# SUSTAINA-Power-Supply-Switching-Board.net
KiCad netlist of a schematic drawn in EAGLE
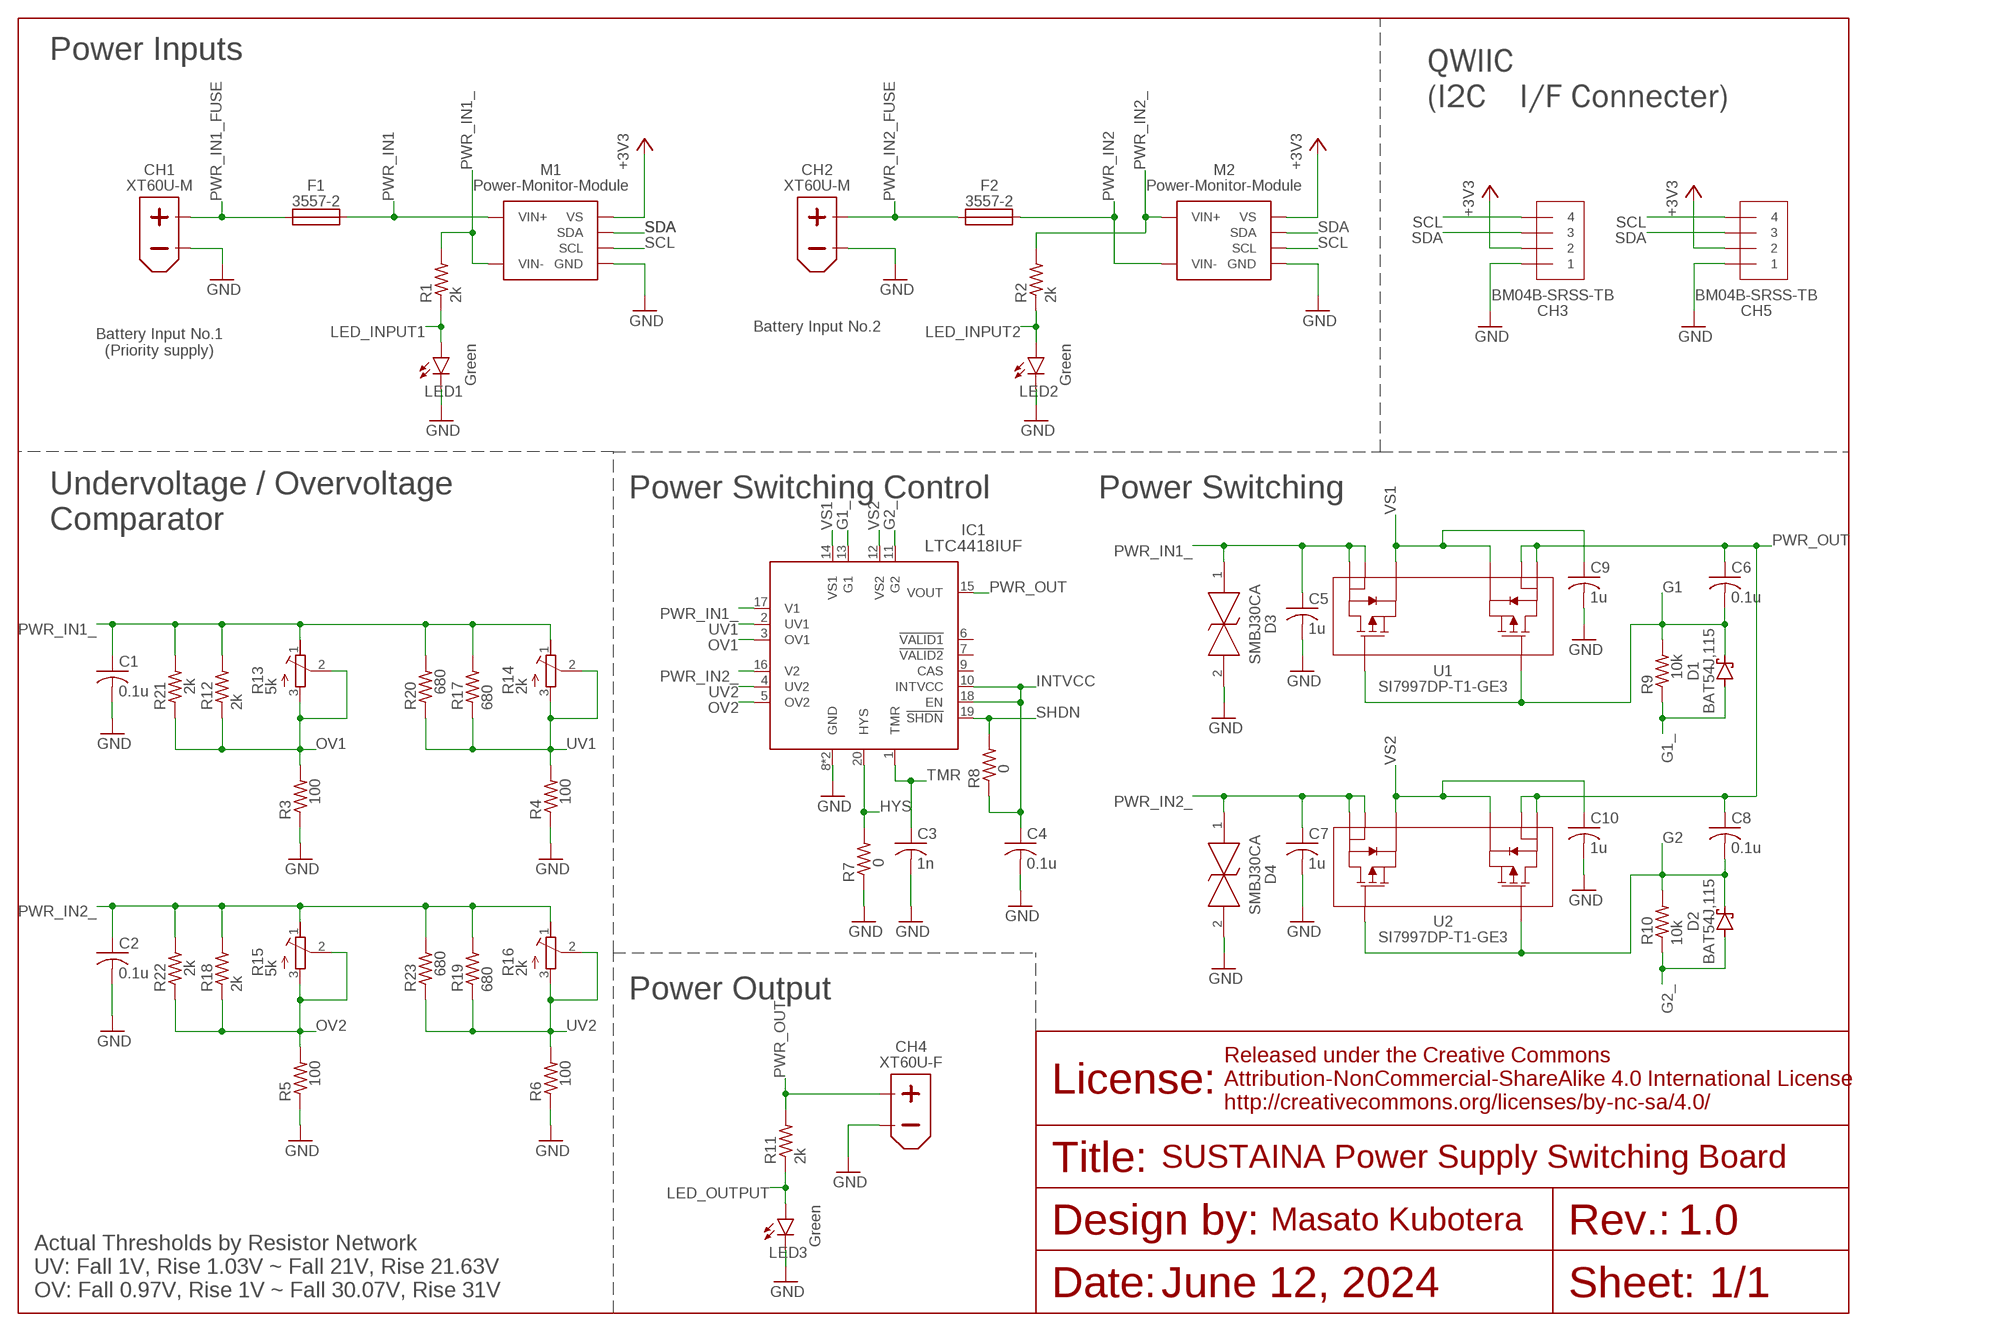
[diagram p0: schematic, sheet 1]

(export (version "E")
  (design (tool "Eeschema 10.0.6"))
  (components
    (comp (ref "C1")
      (value "0.1u")
      (footprint "eagle-import:C0603")
      (libsource (lib "eagle-import") (part "C-USC0603"))
    )
    (comp (ref "C2")
      (value "0.1u")
      (footprint "eagle-import:C0603")
      (libsource (lib "eagle-import") (part "C-USC0603"))
    )
    (comp (ref "C3")
      (value "1n")
      (footprint "eagle-import:C0603")
      (libsource (lib "eagle-import") (part "C-USC0603"))
    )
    (comp (ref "C4")
      (value "0.1u")
      (footprint "eagle-import:C0603")
      (libsource (lib "eagle-import") (part "C-USC0603"))
    )
    (comp (ref "C5")
      (value "1u")
      (footprint "eagle-import:C0603")
      (libsource (lib "eagle-import") (part "C-USC0603"))
    )
    (comp (ref "C6")
      (value "0.1u")
      (footprint "eagle-import:C0603")
      (libsource (lib "eagle-import") (part "C-USC0603"))
    )
    (comp (ref "C7")
      (value "1u")
      (footprint "eagle-import:C0603")
      (libsource (lib "eagle-import") (part "C-USC0603"))
    )
    (comp (ref "C8")
      (value "0.1u")
      (footprint "eagle-import:C0603")
      (libsource (lib "eagle-import") (part "C-USC0603"))
    )
    (comp (ref "C9")
      (value "1u")
      (footprint "eagle-import:C0603")
      (libsource (lib "eagle-import") (part "C-USC0603"))
    )
    (comp (ref "C10")
      (value "1u")
      (footprint "eagle-import:C0603")
      (libsource (lib "eagle-import") (part "C-USC0603"))
    )
    (comp (ref "CH1")
      (value "XT60U-M")
      (footprint "eagle-import:XT60U-M")
      (libsource (lib "eagle-import") (part "XT60U-M"))
    )
    (comp (ref "CH2")
      (value "XT60U-M")
      (footprint "eagle-import:XT60U-M")
      (libsource (lib "eagle-import") (part "XT60U-M"))
    )
    (comp (ref "CH3")
      (value "BM04B-SRSS-TB")
      (footprint "eagle-import:BM04B-SRSS-TB")
      (libsource (lib "eagle-import") (part "BM04B-SRSS-TB"))
    )
    (comp (ref "CH4")
      (value "XT60U-F")
      (footprint "eagle-import:XT60U-F")
      (libsource (lib "eagle-import") (part "XT60U-F"))
    )
    (comp (ref "CH5")
      (value "BM04B-SRSS-TB")
      (footprint "eagle-import:BM04B-SRSS-TB")
      (libsource (lib "eagle-import") (part "BM04B-SRSS-TB"))
    )
    (comp (ref "D1")
      (value "BAT54J,115")
      (footprint "eagle-import:SOD-323-2")
      (libsource (lib "eagle-import") (part "BAT54J,115"))
    )
    (comp (ref "D2")
      (value "BAT54J,115")
      (footprint "eagle-import:SOD-323-2")
      (libsource (lib "eagle-import") (part "BAT54J,115"))
    )
    (comp (ref "D3")
      (value "SMBJ30CA")
      (footprint "eagle-import:SMBJ30CA")
      (libsource (lib "eagle-import") (part "SMBJ30CA"))
    )
    (comp (ref "D4")
      (value "SMBJ30CA")
      (footprint "eagle-import:SMBJ30CA")
      (libsource (lib "eagle-import") (part "SMBJ30CA"))
    )
    (comp (ref "F1")
      (value "3557-2")
      (footprint "eagle-import:3557-2")
      (libsource (lib "eagle-import") (part "3557-2"))
    )
    (comp (ref "F2")
      (value "3557-2")
      (footprint "eagle-import:3557-2")
      (libsource (lib "eagle-import") (part "3557-2"))
    )
    (comp (ref "IC1")
      (value "LTC4418IUF")
      (footprint "eagle-import:LTC4418IUF")
      (libsource (lib "eagle-import") (part "LTC4418IUF"))
    )
    (comp (ref "LED1")
      (value "Green")
      (footprint "eagle-import:SML0603")
      (libsource (lib "eagle-import") (part "LEDSML0603"))
    )
    (comp (ref "LED2")
      (value "Green")
      (footprint "eagle-import:SML0603")
      (libsource (lib "eagle-import") (part "LEDSML0603"))
    )
    (comp (ref "LED3")
      (value "Green")
      (footprint "eagle-import:SML0603")
      (libsource (lib "eagle-import") (part "LEDSML0603"))
    )
    (comp (ref "M1")
      (value "POWER-MONITOR-MODULE")
      (footprint "eagle-import:POWER-MONITOR-MODULE")
      (libsource (lib "eagle-import") (part "POWER-MONITOR-MODULE"))
    )
    (comp (ref "M2")
      (value "POWER-MONITOR-MODULE")
      (footprint "eagle-import:POWER-MONITOR-MODULE")
      (libsource (lib "eagle-import") (part "POWER-MONITOR-MODULE"))
    )
    (comp (ref "R1")
      (value "2k")
      (footprint "eagle-import:R0603")
      (libsource (lib "eagle-import") (part "R-US_R0603"))
    )
    (comp (ref "R2")
      (value "2k")
      (footprint "eagle-import:R0603")
      (libsource (lib "eagle-import") (part "R-US_R0603"))
    )
    (comp (ref "R3")
      (value "100")
      (footprint "eagle-import:R0603")
      (libsource (lib "eagle-import") (part "R-US_R0603"))
    )
    (comp (ref "R4")
      (value "100")
      (footprint "eagle-import:R0603")
      (libsource (lib "eagle-import") (part "R-US_R0603"))
    )
    (comp (ref "R5")
      (value "100")
      (footprint "eagle-import:R0603")
      (libsource (lib "eagle-import") (part "R-US_R0603"))
    )
    (comp (ref "R6")
      (value "100")
      (footprint "eagle-import:R0603")
      (libsource (lib "eagle-import") (part "R-US_R0603"))
    )
    (comp (ref "R7")
      (value "0")
      (footprint "eagle-import:R0603")
      (libsource (lib "eagle-import") (part "R-US_R0603"))
    )
    (comp (ref "R8")
      (value "0")
      (footprint "eagle-import:R0603")
      (libsource (lib "eagle-import") (part "R-US_R0603"))
    )
    (comp (ref "R9")
      (value "10k")
      (footprint "eagle-import:R0603")
      (libsource (lib "eagle-import") (part "R-US_R0603"))
    )
    (comp (ref "R10")
      (value "10k")
      (footprint "eagle-import:R0603")
      (libsource (lib "eagle-import") (part "R-US_R0603"))
    )
    (comp (ref "R11")
      (value "2k")
      (footprint "eagle-import:R0603")
      (libsource (lib "eagle-import") (part "R-US_R0603"))
    )
    (comp (ref "R12")
      (value "2k")
      (footprint "eagle-import:0204_5")
      (libsource (lib "eagle-import") (part "R-US_0204/5"))
    )
    (comp (ref "R13")
      (value "5k")
      (footprint "eagle-import:RTRIM3006P")
      (libsource (lib "eagle-import") (part "R-TRIMM3006P"))
    )
    (comp (ref "R14")
      (value "2k")
      (footprint "eagle-import:RTRIM3006P")
      (libsource (lib "eagle-import") (part "R-TRIMM3006P"))
    )
    (comp (ref "R15")
      (value "5k")
      (footprint "eagle-import:RTRIM3006P")
      (libsource (lib "eagle-import") (part "R-TRIMM3006P"))
    )
    (comp (ref "R16")
      (value "2k")
      (footprint "eagle-import:RTRIM3006P")
      (libsource (lib "eagle-import") (part "R-TRIMM3006P"))
    )
    (comp (ref "R17")
      (value "680")
      (footprint "eagle-import:0204_5")
      (libsource (lib "eagle-import") (part "R-US_0204/5"))
    )
    (comp (ref "R18")
      (value "2k")
      (footprint "eagle-import:0204_5")
      (libsource (lib "eagle-import") (part "R-US_0204/5"))
    )
    (comp (ref "R19")
      (value "680")
      (footprint "eagle-import:0204_5")
      (libsource (lib "eagle-import") (part "R-US_0204/5"))
    )
    (comp (ref "R20")
      (value "680")
      (footprint "eagle-import:R0603")
      (libsource (lib "eagle-import") (part "R-US_R0603"))
    )
    (comp (ref "R21")
      (value "2k")
      (footprint "eagle-import:R0603")
      (libsource (lib "eagle-import") (part "R-US_R0603"))
    )
    (comp (ref "R22")
      (value "2k")
      (footprint "eagle-import:R0603")
      (libsource (lib "eagle-import") (part "R-US_R0603"))
    )
    (comp (ref "R23")
      (value "680")
      (footprint "eagle-import:R0603")
      (libsource (lib "eagle-import") (part "R-US_R0603"))
    )
    (comp (ref "U1")
      (value "SI7997DP-T1-GE3")
      (footprint "eagle-import:POWERPAK_SO-8_VIS")
      (fields (field (name "COPYRIGHT") "Copyright (C) 2024 Ultra Librarian. All rights reserved."))
      (libsource (lib "eagle-import") (part "SI7997DP-T1-GE3"))
    )
    (comp (ref "U2")
      (value "SI7997DP-T1-GE3")
      (footprint "eagle-import:POWERPAK_SO-8_VIS")
      (fields (field (name "COPYRIGHT") "Copyright (C) 2024 Ultra Librarian. All rights reserved."))
      (libsource (lib "eagle-import") (part "SI7997DP-T1-GE3"))
    )
  )
  (nets
    (net (code "1") (name "+3V3") (class "Default")
      (node (ref "CH3") (pin "2") (pinfunction "2_2") (pintype "bidirectional"))
      (node (ref "CH5") (pin "2") (pinfunction "2_2") (pintype "bidirectional"))
      (node (ref "M1") (pin "VS") (pinfunction "VS_VS") (pintype "power_in"))
      (node (ref "M2") (pin "VS") (pinfunction "VS_VS") (pintype "power_in"))
    )
    (net (code "2") (name "/G1") (class "Default")
      (node (ref "C6") (pin "2") (pinfunction "2_2") (pintype "passive"))
      (node (ref "D1") (pin "1") (pinfunction "C_1") (pintype "passive"))
      (node (ref "R9") (pin "2") (pinfunction "2_2") (pintype "passive"))
      (node (ref "U1") (pin "2") (pinfunction "G1_2") (pintype "passive"))
      (node (ref "U1") (pin "4") (pinfunction "G2_4") (pintype "passive"))
    )
    (net (code "3") (name "/G1_") (class "Default")
      (node (ref "D1") (pin "2") (pinfunction "A_2") (pintype "passive"))
      (node (ref "IC1") (pin "13") (pinfunction "G1_13") (pintype "bidirectional"))
      (node (ref "R9") (pin "1") (pinfunction "1_1") (pintype "passive"))
    )
    (net (code "4") (name "/G2") (class "Default")
      (node (ref "C8") (pin "2") (pinfunction "2_2") (pintype "passive"))
      (node (ref "D2") (pin "1") (pinfunction "C_1") (pintype "passive"))
      (node (ref "R10") (pin "2") (pinfunction "2_2") (pintype "passive"))
      (node (ref "U2") (pin "2") (pinfunction "G1_2") (pintype "passive"))
      (node (ref "U2") (pin "4") (pinfunction "G2_4") (pintype "passive"))
    )
    (net (code "5") (name "/G2_") (class "Default")
      (node (ref "D2") (pin "2") (pinfunction "A_2") (pintype "passive"))
      (node (ref "IC1") (pin "11") (pinfunction "G2_11") (pintype "bidirectional"))
      (node (ref "R10") (pin "1") (pinfunction "1_1") (pintype "passive"))
    )
    (net (code "6") (name "/HYS") (class "Default")
      (node (ref "IC1") (pin "20") (pinfunction "HYS_20") (pintype "bidirectional"))
      (node (ref "R7") (pin "2") (pinfunction "2_2") (pintype "passive"))
    )
    (net (code "7") (name "/INTVCC") (class "Default")
      (node (ref "C4") (pin "1") (pinfunction "1_1") (pintype "passive"))
      (node (ref "IC1") (pin "10") (pinfunction "INTVCC_10") (pintype "bidirectional"))
      (node (ref "IC1") (pin "18") (pinfunction "EN_18") (pintype "bidirectional"))
      (node (ref "R8") (pin "1") (pinfunction "1_1") (pintype "passive"))
    )
    (net (code "8") (name "/LED_INPUT1") (class "Default")
      (node (ref "LED1") (pin "A") (pinfunction "A_A") (pintype "passive"))
      (node (ref "R1") (pin "1") (pinfunction "1_1") (pintype "passive"))
    )
    (net (code "9") (name "/LED_INPUT2") (class "Default")
      (node (ref "LED2") (pin "A") (pinfunction "A_A") (pintype "passive"))
      (node (ref "R2") (pin "1") (pinfunction "1_1") (pintype "passive"))
    )
    (net (code "10") (name "/LED_OUTPUT") (class "Default")
      (node (ref "LED3") (pin "A") (pinfunction "A_A") (pintype "passive"))
      (node (ref "R11") (pin "1") (pinfunction "1_1") (pintype "passive"))
    )
    (net (code "11") (name "/OV1") (class "Default")
      (node (ref "IC1") (pin "3") (pinfunction "OV1_3") (pintype "bidirectional"))
      (node (ref "R12") (pin "1") (pinfunction "1_1") (pintype "passive"))
      (node (ref "R13") (pin "2") (pinfunction "S_2") (pintype "passive"))
      (node (ref "R13") (pin "3") (pinfunction "A_3") (pintype "passive"))
      (node (ref "R21") (pin "1") (pinfunction "1_1") (pintype "passive"))
      (node (ref "R3") (pin "2") (pinfunction "2_2") (pintype "passive"))
    )
    (net (code "12") (name "/OV2") (class "Default")
      (node (ref "IC1") (pin "5") (pinfunction "OV2_5") (pintype "bidirectional"))
      (node (ref "R15") (pin "2") (pinfunction "S_2") (pintype "passive"))
      (node (ref "R15") (pin "3") (pinfunction "A_3") (pintype "passive"))
      (node (ref "R18") (pin "1") (pinfunction "1_1") (pintype "passive"))
      (node (ref "R22") (pin "1") (pinfunction "1_1") (pintype "passive"))
      (node (ref "R5") (pin "2") (pinfunction "2_2") (pintype "passive"))
    )
    (net (code "13") (name "/PWR_IN1") (class "Default")
      (node (ref "F1") (pin "3") (pinfunction "2_3") (pintype "bidirectional"))
      (node (ref "F1") (pin "4") (pinfunction "2_4") (pintype "bidirectional"))
      (node (ref "M1") (pin "VIN+1") (pinfunction "VIN+_VIN+1") (pintype "power_in"))
      (node (ref "M1") (pin "VIN+10") (pinfunction "VIN+_VIN+10") (pintype "power_in"))
      (node (ref "M1") (pin "VIN+2") (pinfunction "VIN+_VIN+2") (pintype "power_in"))
      (node (ref "M1") (pin "VIN+3") (pinfunction "VIN+_VIN+3") (pintype "power_in"))
      (node (ref "M1") (pin "VIN+4") (pinfunction "VIN+_VIN+4") (pintype "power_in"))
      (node (ref "M1") (pin "VIN+5") (pinfunction "VIN+_VIN+5") (pintype "power_in"))
      (node (ref "M1") (pin "VIN+6") (pinfunction "VIN+_VIN+6") (pintype "power_in"))
      (node (ref "M1") (pin "VIN+7") (pinfunction "VIN+_VIN+7") (pintype "power_in"))
      (node (ref "M1") (pin "VIN+8") (pinfunction "VIN+_VIN+8") (pintype "power_in"))
      (node (ref "M1") (pin "VIN+9") (pinfunction "VIN+_VIN+9") (pintype "power_in"))
    )
    (net (code "14") (name "/PWR_IN1_") (class "Default")
      (node (ref "C1") (pin "1") (pinfunction "1_1") (pintype "passive"))
      (node (ref "C5") (pin "1") (pinfunction "1_1") (pintype "passive"))
      (node (ref "D3") (pin "1") (pinfunction "1_1") (pintype "bidirectional"))
      (node (ref "IC1") (pin "17") (pinfunction "V1_17") (pintype "bidirectional"))
      (node (ref "M1") (pin "VIN-1") (pinfunction "VIN-_VIN-1") (pintype "power_in"))
      (node (ref "M1") (pin "VIN-10") (pinfunction "VIN-_VIN-10") (pintype "power_in"))
      (node (ref "M1") (pin "VIN-2") (pinfunction "VIN-_VIN-2") (pintype "power_in"))
      (node (ref "M1") (pin "VIN-3") (pinfunction "VIN-_VIN-3") (pintype "power_in"))
      (node (ref "M1") (pin "VIN-4") (pinfunction "VIN-_VIN-4") (pintype "power_in"))
      (node (ref "M1") (pin "VIN-5") (pinfunction "VIN-_VIN-5") (pintype "power_in"))
      (node (ref "M1") (pin "VIN-6") (pinfunction "VIN-_VIN-6") (pintype "power_in"))
      (node (ref "M1") (pin "VIN-7") (pinfunction "VIN-_VIN-7") (pintype "power_in"))
      (node (ref "M1") (pin "VIN-8") (pinfunction "VIN-_VIN-8") (pintype "power_in"))
      (node (ref "M1") (pin "VIN-9") (pinfunction "VIN-_VIN-9") (pintype "power_in"))
      (node (ref "R1") (pin "2") (pinfunction "2_2") (pintype "passive"))
      (node (ref "R12") (pin "2") (pinfunction "2_2") (pintype "passive"))
      (node (ref "R13") (pin "1") (pinfunction "E_1") (pintype "passive"))
      (node (ref "R14") (pin "1") (pinfunction "E_1") (pintype "passive"))
      (node (ref "R17") (pin "2") (pinfunction "2_2") (pintype "passive"))
      (node (ref "R20") (pin "2") (pinfunction "2_2") (pintype "passive"))
      (node (ref "R21") (pin "2") (pinfunction "2_2") (pintype "passive"))
      (node (ref "U1") (pin "5") (pinfunction "D2_5") (pintype "passive"))
      (node (ref "U1") (pin "6") (pinfunction "D2_2_6") (pintype "passive"))
    )
    (net (code "15") (name "/PWR_IN1_FUSE") (class "Default")
      (node (ref "CH1") (pin "+") (pinfunction "+_+") (pintype "power_in"))
      (node (ref "F1") (pin "1") (pinfunction "1_1") (pintype "bidirectional"))
      (node (ref "F1") (pin "2") (pinfunction "1_2") (pintype "bidirectional"))
    )
    (net (code "16") (name "/PWR_IN2") (class "Default")
      (node (ref "F2") (pin "3") (pinfunction "2_3") (pintype "bidirectional"))
      (node (ref "F2") (pin "4") (pinfunction "2_4") (pintype "bidirectional"))
      (node (ref "M2") (pin "VIN-1") (pinfunction "VIN-_VIN-1") (pintype "power_in"))
      (node (ref "M2") (pin "VIN-10") (pinfunction "VIN-_VIN-10") (pintype "power_in"))
      (node (ref "M2") (pin "VIN-2") (pinfunction "VIN-_VIN-2") (pintype "power_in"))
      (node (ref "M2") (pin "VIN-3") (pinfunction "VIN-_VIN-3") (pintype "power_in"))
      (node (ref "M2") (pin "VIN-4") (pinfunction "VIN-_VIN-4") (pintype "power_in"))
      (node (ref "M2") (pin "VIN-5") (pinfunction "VIN-_VIN-5") (pintype "power_in"))
      (node (ref "M2") (pin "VIN-6") (pinfunction "VIN-_VIN-6") (pintype "power_in"))
      (node (ref "M2") (pin "VIN-7") (pinfunction "VIN-_VIN-7") (pintype "power_in"))
      (node (ref "M2") (pin "VIN-8") (pinfunction "VIN-_VIN-8") (pintype "power_in"))
      (node (ref "M2") (pin "VIN-9") (pinfunction "VIN-_VIN-9") (pintype "power_in"))
    )
    (net (code "17") (name "/PWR_IN2_") (class "Default")
      (node (ref "C2") (pin "1") (pinfunction "1_1") (pintype "passive"))
      (node (ref "C7") (pin "1") (pinfunction "1_1") (pintype "passive"))
      (node (ref "D4") (pin "1") (pinfunction "1_1") (pintype "bidirectional"))
      (node (ref "IC1") (pin "16") (pinfunction "V2_16") (pintype "bidirectional"))
      (node (ref "M2") (pin "VIN+1") (pinfunction "VIN+_VIN+1") (pintype "power_in"))
      (node (ref "M2") (pin "VIN+10") (pinfunction "VIN+_VIN+10") (pintype "power_in"))
      (node (ref "M2") (pin "VIN+2") (pinfunction "VIN+_VIN+2") (pintype "power_in"))
      (node (ref "M2") (pin "VIN+3") (pinfunction "VIN+_VIN+3") (pintype "power_in"))
      (node (ref "M2") (pin "VIN+4") (pinfunction "VIN+_VIN+4") (pintype "power_in"))
      (node (ref "M2") (pin "VIN+5") (pinfunction "VIN+_VIN+5") (pintype "power_in"))
      (node (ref "M2") (pin "VIN+6") (pinfunction "VIN+_VIN+6") (pintype "power_in"))
      (node (ref "M2") (pin "VIN+7") (pinfunction "VIN+_VIN+7") (pintype "power_in"))
      (node (ref "M2") (pin "VIN+8") (pinfunction "VIN+_VIN+8") (pintype "power_in"))
      (node (ref "M2") (pin "VIN+9") (pinfunction "VIN+_VIN+9") (pintype "power_in"))
      (node (ref "R15") (pin "1") (pinfunction "E_1") (pintype "passive"))
      (node (ref "R16") (pin "1") (pinfunction "E_1") (pintype "passive"))
      (node (ref "R18") (pin "2") (pinfunction "2_2") (pintype "passive"))
      (node (ref "R19") (pin "2") (pinfunction "2_2") (pintype "passive"))
      (node (ref "R2") (pin "2") (pinfunction "2_2") (pintype "passive"))
      (node (ref "R22") (pin "2") (pinfunction "2_2") (pintype "passive"))
      (node (ref "R23") (pin "2") (pinfunction "2_2") (pintype "passive"))
      (node (ref "U2") (pin "7") (pinfunction "D1_7") (pintype "passive"))
      (node (ref "U2") (pin "8") (pinfunction "D1_2_8") (pintype "passive"))
    )
    (net (code "18") (name "/PWR_IN2_FUSE") (class "Default")
      (node (ref "CH2") (pin "+") (pinfunction "+_+") (pintype "power_in"))
      (node (ref "F2") (pin "1") (pinfunction "1_1") (pintype "bidirectional"))
      (node (ref "F2") (pin "2") (pinfunction "1_2") (pintype "bidirectional"))
    )
    (net (code "19") (name "/PWR_OUT") (class "Default")
      (node (ref "C6") (pin "1") (pinfunction "1_1") (pintype "passive"))
      (node (ref "C8") (pin "1") (pinfunction "1_1") (pintype "passive"))
      (node (ref "CH4") (pin "+") (pinfunction "+_+") (pintype "power_in"))
      (node (ref "IC1") (pin "15") (pinfunction "VOUT_15") (pintype "bidirectional"))
      (node (ref "R11") (pin "2") (pinfunction "2_2") (pintype "passive"))
      (node (ref "U1") (pin "7") (pinfunction "D1_7") (pintype "passive"))
      (node (ref "U1") (pin "8") (pinfunction "D1_2_8") (pintype "passive"))
      (node (ref "U2") (pin "5") (pinfunction "D2_5") (pintype "passive"))
      (node (ref "U2") (pin "6") (pinfunction "D2_2_6") (pintype "passive"))
    )
    (net (code "20") (name "/SCL") (class "Default")
      (node (ref "CH3") (pin "4") (pinfunction "4_4") (pintype "bidirectional"))
      (node (ref "CH5") (pin "4") (pinfunction "4_4") (pintype "bidirectional"))
      (node (ref "M1") (pin "SCL") (pinfunction "SCL_SCL") (pintype "bidirectional"))
      (node (ref "M2") (pin "SCL") (pinfunction "SCL_SCL") (pintype "bidirectional"))
    )
    (net (code "21") (name "/SDA") (class "Default")
      (node (ref "CH3") (pin "3") (pinfunction "3_3") (pintype "bidirectional"))
      (node (ref "CH5") (pin "3") (pinfunction "3_3") (pintype "bidirectional"))
      (node (ref "M1") (pin "SDA") (pinfunction "SDA_SDA") (pintype "bidirectional"))
      (node (ref "M2") (pin "SDA") (pinfunction "SDA_SDA") (pintype "bidirectional"))
    )
    (net (code "22") (name "/SHDN") (class "Default")
      (node (ref "IC1") (pin "19") (pinfunction "~{SHDN}_19") (pintype "bidirectional"))
      (node (ref "R8") (pin "2") (pinfunction "2_2") (pintype "passive"))
    )
    (net (code "23") (name "/TMR") (class "Default")
      (node (ref "C3") (pin "1") (pinfunction "1_1") (pintype "passive"))
      (node (ref "IC1") (pin "1") (pinfunction "TMR_1") (pintype "bidirectional"))
    )
    (net (code "24") (name "/UV1") (class "Default")
      (node (ref "IC1") (pin "2") (pinfunction "UV1_2") (pintype "bidirectional"))
      (node (ref "R14") (pin "2") (pinfunction "S_2") (pintype "passive"))
      (node (ref "R14") (pin "3") (pinfunction "A_3") (pintype "passive"))
      (node (ref "R17") (pin "1") (pinfunction "1_1") (pintype "passive"))
      (node (ref "R20") (pin "1") (pinfunction "1_1") (pintype "passive"))
      (node (ref "R4") (pin "2") (pinfunction "2_2") (pintype "passive"))
    )
    (net (code "25") (name "/UV2") (class "Default")
      (node (ref "IC1") (pin "4") (pinfunction "UV2_4") (pintype "bidirectional"))
      (node (ref "R16") (pin "2") (pinfunction "S_2") (pintype "passive"))
      (node (ref "R16") (pin "3") (pinfunction "A_3") (pintype "passive"))
      (node (ref "R19") (pin "1") (pinfunction "1_1") (pintype "passive"))
      (node (ref "R23") (pin "1") (pinfunction "1_1") (pintype "passive"))
      (node (ref "R6") (pin "2") (pinfunction "2_2") (pintype "passive"))
    )
    (net (code "26") (name "/VS1") (class "Default")
      (node (ref "C9") (pin "1") (pinfunction "1_1") (pintype "passive"))
      (node (ref "IC1") (pin "14") (pinfunction "VS1_14") (pintype "bidirectional"))
      (node (ref "U1") (pin "1") (pinfunction "S1_1") (pintype "passive"))
      (node (ref "U1") (pin "3") (pinfunction "S2_3") (pintype "passive"))
    )
    (net (code "27") (name "/VS2") (class "Default")
      (node (ref "C10") (pin "1") (pinfunction "1_1") (pintype "passive"))
      (node (ref "IC1") (pin "12") (pinfunction "VS2_12") (pintype "bidirectional"))
      (node (ref "U2") (pin "1") (pinfunction "S1_1") (pintype "passive"))
      (node (ref "U2") (pin "3") (pinfunction "S2_3") (pintype "passive"))
    )
    (net (code "28") (name "GND") (class "Default")
      (node (ref "C1") (pin "2") (pinfunction "2_2") (pintype "passive"))
      (node (ref "C10") (pin "2") (pinfunction "2_2") (pintype "passive"))
      (node (ref "C2") (pin "2") (pinfunction "2_2") (pintype "passive"))
      (node (ref "C3") (pin "2") (pinfunction "2_2") (pintype "passive"))
      (node (ref "C4") (pin "2") (pinfunction "2_2") (pintype "passive"))
      (node (ref "C5") (pin "2") (pinfunction "2_2") (pintype "passive"))
      (node (ref "C7") (pin "2") (pinfunction "2_2") (pintype "passive"))
      (node (ref "C9") (pin "2") (pinfunction "2_2") (pintype "passive"))
      (node (ref "CH1") (pin "-") (pinfunction "-_-") (pintype "power_in"))
      (node (ref "CH2") (pin "-") (pinfunction "-_-") (pintype "power_in"))
      (node (ref "CH3") (pin "1") (pinfunction "1_1") (pintype "bidirectional"))
      (node (ref "CH4") (pin "-") (pinfunction "-_-") (pintype "power_in"))
      (node (ref "CH5") (pin "1") (pinfunction "1_1") (pintype "bidirectional"))
      (node (ref "D3") (pin "2") (pinfunction "2_2") (pintype "bidirectional"))
      (node (ref "D4") (pin "2") (pinfunction "2_2") (pintype "bidirectional"))
      (node (ref "IC1") (pin "21") (pinfunction "GND_21") (pintype "bidirectional"))
      (node (ref "IC1") (pin "8") (pinfunction "GND_8") (pintype "bidirectional"))
      (node (ref "LED1") (pin "C") (pinfunction "C_C") (pintype "passive"))
      (node (ref "LED2") (pin "C") (pinfunction "C_C") (pintype "passive"))
      (node (ref "LED3") (pin "C") (pinfunction "C_C") (pintype "passive"))
      (node (ref "M1") (pin "GND") (pinfunction "GND_GND") (pintype "power_in"))
      (node (ref "M2") (pin "GND") (pinfunction "GND_GND") (pintype "power_in"))
      (node (ref "R3") (pin "1") (pinfunction "1_1") (pintype "passive"))
      (node (ref "R4") (pin "1") (pinfunction "1_1") (pintype "passive"))
      (node (ref "R5") (pin "1") (pinfunction "1_1") (pintype "passive"))
      (node (ref "R6") (pin "1") (pinfunction "1_1") (pintype "passive"))
      (node (ref "R7") (pin "1") (pinfunction "1_1") (pintype "passive"))
    )
    (net (code "29") (name "unconnected-(IC1-CAS-Pad9)") (class "Default")
      (node (ref "IC1") (pin "9") (pinfunction "CAS_9") (pintype "bidirectional"))
    )
    (net (code "30") (name "unconnected-(IC1-~{VALID1}-Pad6)") (class "Default")
      (node (ref "IC1") (pin "6") (pinfunction "~{VALID1}_6") (pintype "bidirectional"))
    )
    (net (code "31") (name "unconnected-(IC1-~{VALID2}-Pad7)") (class "Default")
      (node (ref "IC1") (pin "7") (pinfunction "~{VALID2}_7") (pintype "bidirectional"))
    )
  )
)
